# audio.net
KiCad netlist of a schematic drawn in EAGLE
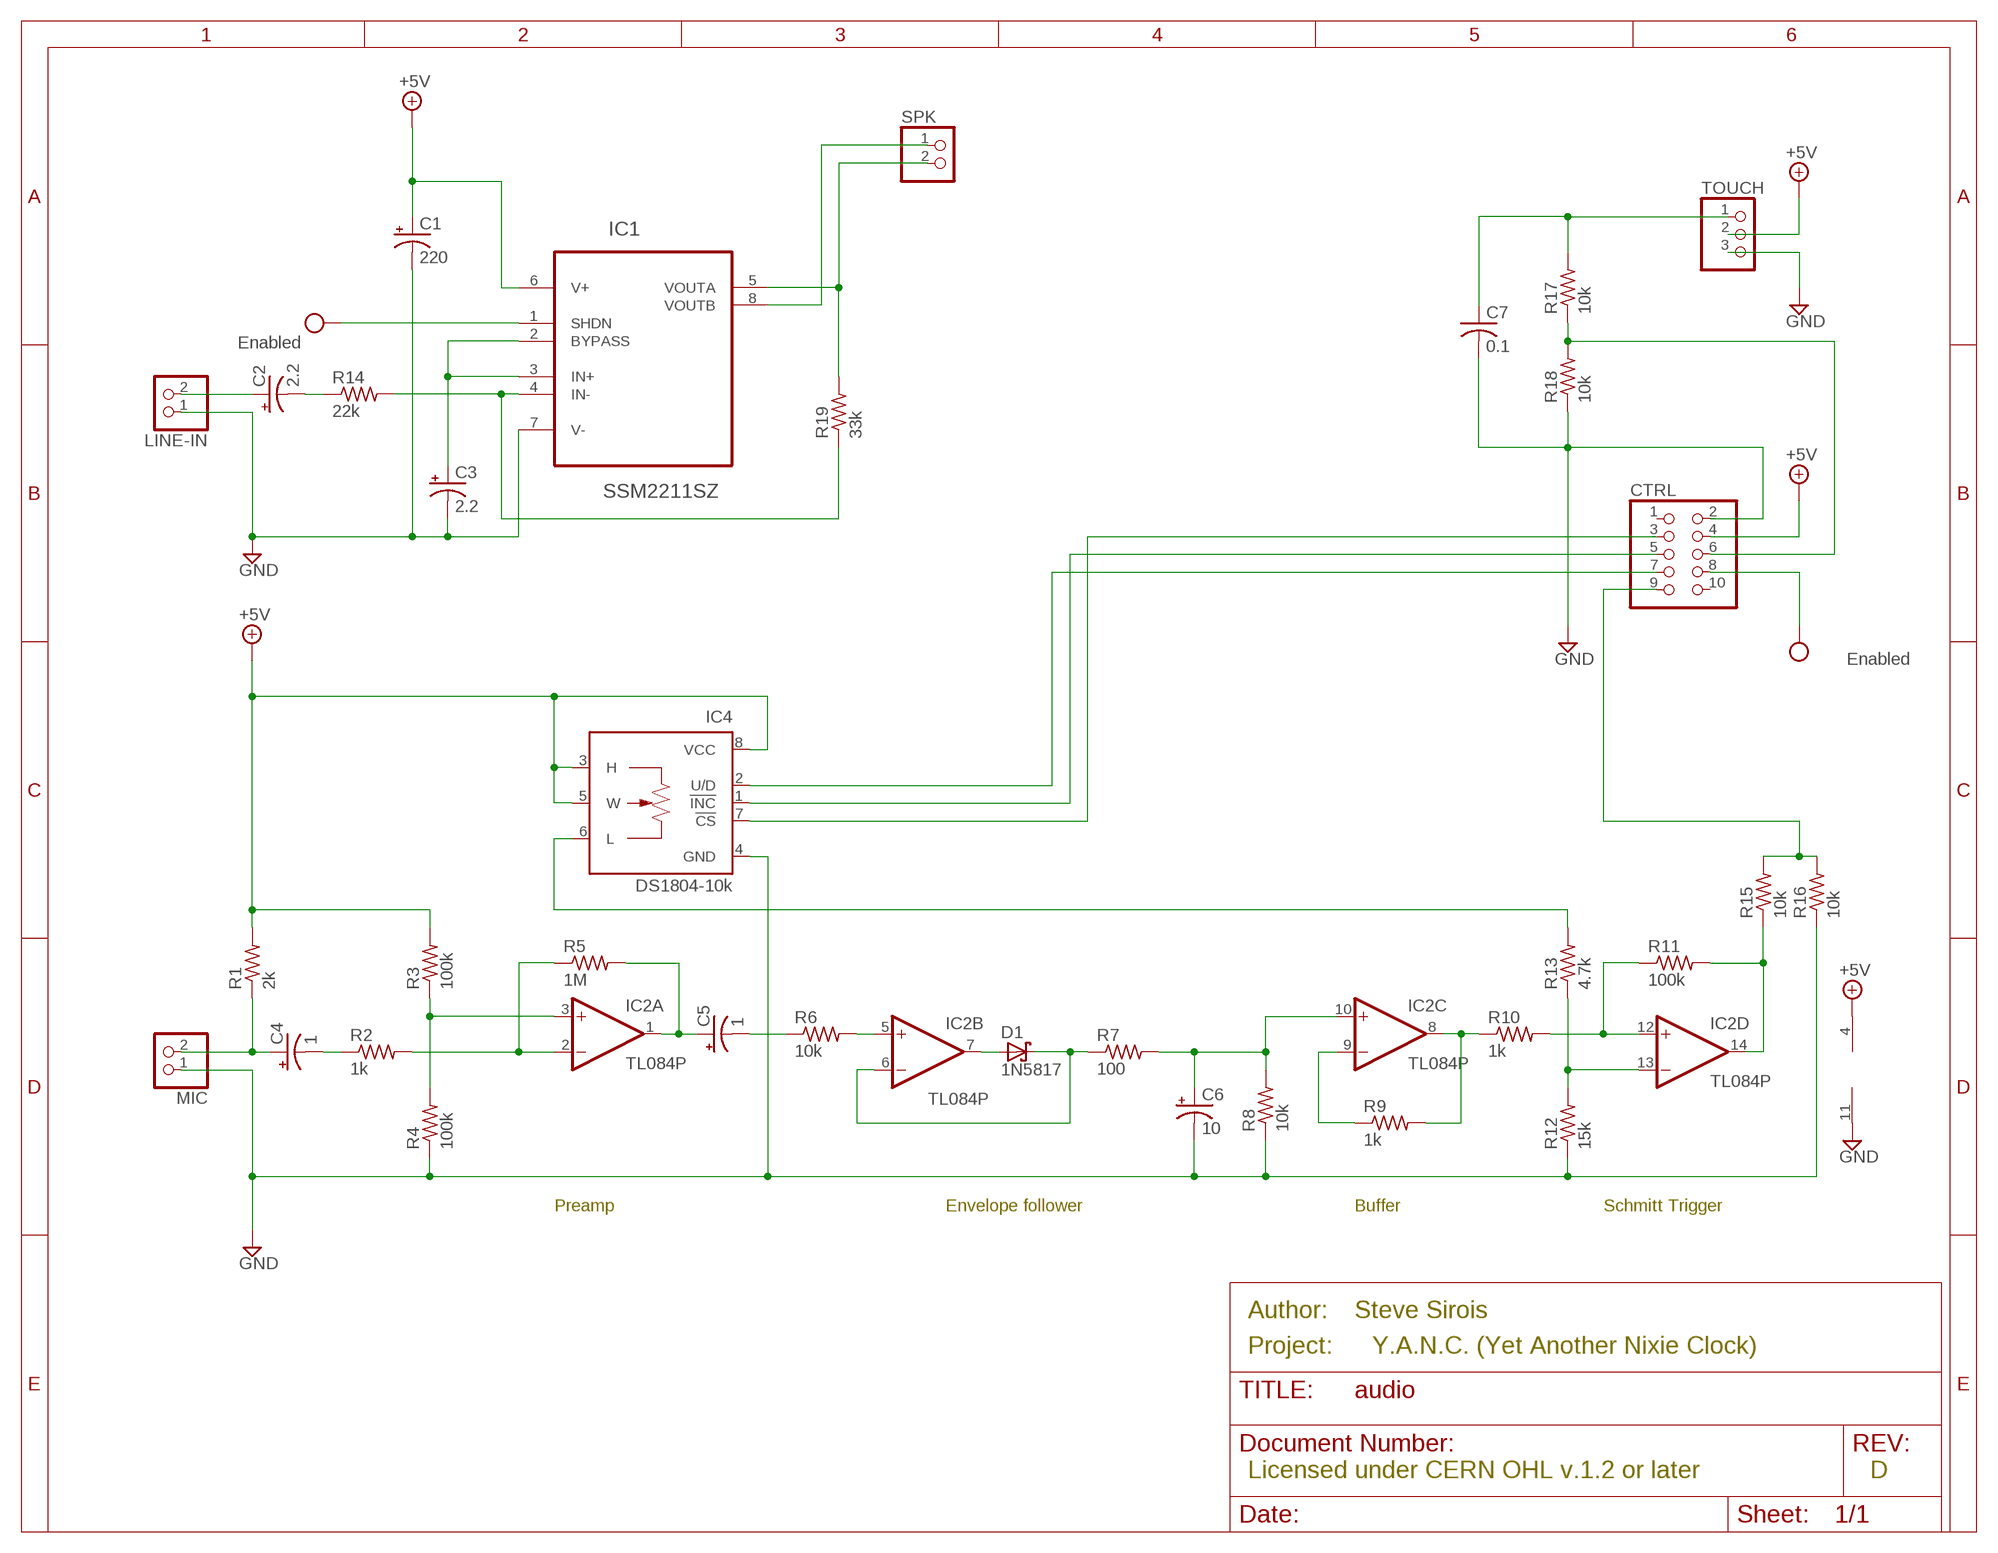
[diagram p0: schematic, sheet 1]

(export (version "E")
  (design (tool "Eeschema 10.0.6"))
  (components
    (comp (ref "C1")
      (value "220")
      (footprint "eagle-import:E3,5-10")
      (libsource (lib "eagle-import") (part "CPOL-USE3.5-10"))
    )
    (comp (ref "C2")
      (value "2.2")
      (footprint "eagle-import:E3,5-8")
      (libsource (lib "eagle-import") (part "CPOL-USE3.5-8"))
    )
    (comp (ref "C3")
      (value "2.2")
      (footprint "eagle-import:E3,5-8")
      (libsource (lib "eagle-import") (part "CPOL-USE3.5-8"))
    )
    (comp (ref "C4")
      (value "1")
      (footprint "eagle-import:E2-4")
      (libsource (lib "eagle-import") (part "CPOL-USE2-4"))
    )
    (comp (ref "C5")
      (value "1")
      (footprint "eagle-import:E2-4")
      (libsource (lib "eagle-import") (part "CPOL-USE2-4"))
    )
    (comp (ref "C6")
      (value "10")
      (footprint "eagle-import:E2-4")
      (libsource (lib "eagle-import") (part "CPOL-USE2-4"))
    )
    (comp (ref "C7")
      (value "0.1")
      (footprint "eagle-import:C025-024X044")
      (libsource (lib "eagle-import") (part "C-US025-024X044"))
    )
    (comp (ref "CTRL")
      (value "PINHD-2X5")
      (footprint "eagle-import:2X05")
      (libsource (lib "eagle-import") (part "PINHD-2X5"))
    )
    (comp (ref "D1")
      (value "1N5817")
      (footprint "eagle-import:DO41-7")
      (libsource (lib "eagle-import") (part "SCHOTTKY-DIODEDO41-7"))
    )
    (comp (ref "IC1")
      (value "SSM2211SZ")
      (footprint "eagle-import:SOIC127P600X175-8N")
      (libsource (lib "eagle-import") (part "SSM2211SZ"))
    )
    (comp (ref "IC2")
      (value "TL084P")
      (footprint "eagle-import:DIL14")
      (libsource (lib "eagle-import") (part "TL084P"))
    )
    (comp (ref "IC4")
      (value "DS1804-10k")
      (footprint "eagle-import:DIL08")
      (fields (field (name "MF") "INTERSIL") (field (name "MPN") "X9C102P"))
      (libsource (lib "eagle-import") (part "X9C102P"))
    )
    (comp (ref "LINE-IN")
      (value "PINHD-1X2")
      (footprint "eagle-import:1X02")
      (libsource (lib "eagle-import") (part "PINHD-1X2"))
    )
    (comp (ref "MIC")
      (value "PINHD-1X2")
      (footprint "eagle-import:1X02")
      (libsource (lib "eagle-import") (part "PINHD-1X2"))
    )
    (comp (ref "R1")
      (value "2k")
      (footprint "eagle-import:0204V")
      (libsource (lib "eagle-import") (part "R-US_0204/2V"))
    )
    (comp (ref "R2")
      (value "1k")
      (footprint "eagle-import:0204V")
      (libsource (lib "eagle-import") (part "R-US_0204/2V"))
    )
    (comp (ref "R3")
      (value "100k")
      (footprint "eagle-import:0204V")
      (libsource (lib "eagle-import") (part "R-US_0204/2V"))
    )
    (comp (ref "R4")
      (value "100k")
      (footprint "eagle-import:0204V")
      (libsource (lib "eagle-import") (part "R-US_0204/2V"))
    )
    (comp (ref "R5")
      (value "1M")
      (footprint "eagle-import:0204V")
      (libsource (lib "eagle-import") (part "R-US_0204/2V"))
    )
    (comp (ref "R6")
      (value "10k")
      (footprint "eagle-import:0204V")
      (libsource (lib "eagle-import") (part "R-US_0204/2V"))
    )
    (comp (ref "R7")
      (value "100")
      (footprint "eagle-import:0204V")
      (libsource (lib "eagle-import") (part "R-US_0204/2V"))
    )
    (comp (ref "R8")
      (value "10k")
      (footprint "eagle-import:0204V")
      (libsource (lib "eagle-import") (part "R-US_0204/2V"))
    )
    (comp (ref "R9")
      (value "1k")
      (footprint "eagle-import:0204V")
      (libsource (lib "eagle-import") (part "R-US_0204/2V"))
    )
    (comp (ref "R10")
      (value "1k")
      (footprint "eagle-import:0204V")
      (libsource (lib "eagle-import") (part "R-US_0204/2V"))
    )
    (comp (ref "R11")
      (value "100k")
      (footprint "eagle-import:0204V")
      (libsource (lib "eagle-import") (part "R-US_0204/2V"))
    )
    (comp (ref "R12")
      (value "15k")
      (footprint "eagle-import:0204V")
      (libsource (lib "eagle-import") (part "R-US_0204/2V"))
    )
    (comp (ref "R13")
      (value "4.7k")
      (footprint "eagle-import:0204V")
      (libsource (lib "eagle-import") (part "R-US_0204/2V"))
    )
    (comp (ref "R14")
      (value "22k")
      (footprint "eagle-import:0204V")
      (libsource (lib "eagle-import") (part "R-US_0204/2V"))
    )
    (comp (ref "R15")
      (value "10k")
      (footprint "eagle-import:0204V")
      (libsource (lib "eagle-import") (part "R-US_0204/2V"))
    )
    (comp (ref "R16")
      (value "10k")
      (footprint "eagle-import:0204V")
      (libsource (lib "eagle-import") (part "R-US_0204/2V"))
    )
    (comp (ref "R17")
      (value "10k")
      (footprint "eagle-import:0204V")
      (libsource (lib "eagle-import") (part "R-US_0204/2V"))
    )
    (comp (ref "R18")
      (value "10k")
      (footprint "eagle-import:0204V")
      (libsource (lib "eagle-import") (part "R-US_0204/2V"))
    )
    (comp (ref "R19")
      (value "33k")
      (footprint "eagle-import:0204V")
      (libsource (lib "eagle-import") (part "R-US_0204/2V"))
    )
    (comp (ref "SPK")
      (value "PINHD-1X2")
      (footprint "eagle-import:1X02")
      (libsource (lib "eagle-import") (part "PINHD-1X2"))
    )
    (comp (ref "TOUCH")
      (value "PINHD-1X3")
      (footprint "eagle-import:1X03")
      (libsource (lib "eagle-import") (part "PINHD-1X3"))
    )
  )
  (nets
    (net (code "1") (name "+5V") (class "Default")
      (node (ref "C1") (pin "+") (pinfunction "+_+") (pintype "passive"))
      (node (ref "CTRL") (pin "4") (pinfunction "4_4") (pintype "passive"))
      (node (ref "IC1") (pin "6") (pinfunction "V+_6") (pintype "power_in"))
      (node (ref "IC2") (pin "4") (pinfunction "V+_4") (pintype "power_in"))
      (node (ref "IC4") (pin "3") (pinfunction "H_3") (pintype "passive"))
      (node (ref "IC4") (pin "5") (pinfunction "W_5") (pintype "passive"))
      (node (ref "IC4") (pin "8") (pinfunction "VCC_8") (pintype "power_in"))
      (node (ref "R1") (pin "2") (pinfunction "2_2") (pintype "passive"))
      (node (ref "R3") (pin "2") (pinfunction "2_2") (pintype "passive"))
      (node (ref "TOUCH") (pin "2") (pinfunction "2_2") (pintype "passive"))
    )
    (net (code "2") (name "Enabled") (class "Default")
      (node (ref "CTRL") (pin "8") (pinfunction "8_8") (pintype "passive"))
      (node (ref "IC1") (pin "1") (pinfunction "SHDN_1") (pintype "passive"))
    )
    (net (code "3") (name "GND") (class "Default")
      (node (ref "C1") (pin "-") (pinfunction "-_-") (pintype "passive"))
      (node (ref "C3") (pin "-") (pinfunction "-_-") (pintype "passive"))
      (node (ref "C6") (pin "-") (pinfunction "-_-") (pintype "passive"))
      (node (ref "C7") (pin "2") (pinfunction "2_2") (pintype "passive"))
      (node (ref "CTRL") (pin "2") (pinfunction "2_2") (pintype "passive"))
      (node (ref "IC1") (pin "7") (pinfunction "V-_7") (pintype "power_in"))
      (node (ref "IC2") (pin "11") (pinfunction "V-_11") (pintype "power_in"))
      (node (ref "IC4") (pin "4") (pinfunction "GND_4") (pintype "power_in"))
      (node (ref "LINE-IN") (pin "1") (pinfunction "1_1") (pintype "passive"))
      (node (ref "MIC") (pin "1") (pinfunction "1_1") (pintype "passive"))
      (node (ref "R12") (pin "1") (pinfunction "1_1") (pintype "passive"))
      (node (ref "R16") (pin "1") (pinfunction "1_1") (pintype "passive"))
      (node (ref "R18") (pin "1") (pinfunction "1_1") (pintype "passive"))
      (node (ref "R4") (pin "1") (pinfunction "1_1") (pintype "passive"))
      (node (ref "R8") (pin "1") (pinfunction "1_1") (pintype "passive"))
      (node (ref "TOUCH") (pin "3") (pinfunction "3_3") (pintype "passive"))
    )
    (net (code "4") (name "Net-(C2-Pad+)") (class "Default")
      (node (ref "C2") (pin "+") (pinfunction "+_+") (pintype "passive"))
      (node (ref "LINE-IN") (pin "2") (pinfunction "2_2") (pintype "passive"))
    )
    (net (code "5") (name "Net-(C2-Pad-)") (class "Default")
      (node (ref "C2") (pin "-") (pinfunction "-_-") (pintype "passive"))
      (node (ref "R14") (pin "1") (pinfunction "1_1") (pintype "passive"))
    )
    (net (code "6") (name "Net-(C4-Pad+)") (class "Default")
      (node (ref "C4") (pin "+") (pinfunction "+_+") (pintype "passive"))
      (node (ref "MIC") (pin "2") (pinfunction "2_2") (pintype "passive"))
      (node (ref "R1") (pin "1") (pinfunction "1_1") (pintype "passive"))
    )
    (net (code "7") (name "Net-(C4-Pad-)") (class "Default")
      (node (ref "C4") (pin "-") (pinfunction "-_-") (pintype "passive"))
      (node (ref "R2") (pin "1") (pinfunction "1_1") (pintype "passive"))
    )
    (net (code "8") (name "Net-(C5-Pad-)") (class "Default")
      (node (ref "C5") (pin "-") (pinfunction "-_-") (pintype "passive"))
      (node (ref "R6") (pin "1") (pinfunction "1_1") (pintype "passive"))
    )
    (net (code "9") (name "Net-(C7-Pad1)") (class "Default")
      (node (ref "C7") (pin "1") (pinfunction "1_1") (pintype "passive"))
      (node (ref "R17") (pin "2") (pinfunction "2_2") (pintype "passive"))
      (node (ref "TOUCH") (pin "1") (pinfunction "1_1") (pintype "passive"))
    )
    (net (code "10") (name "Net-(CTRL-Pad6)") (class "Default")
      (node (ref "CTRL") (pin "6") (pinfunction "6_6") (pintype "passive"))
      (node (ref "R17") (pin "1") (pinfunction "1_1") (pintype "passive"))
      (node (ref "R18") (pin "2") (pinfunction "2_2") (pintype "passive"))
    )
    (net (code "11") (name "Net-(CTRL-Pad9)") (class "Default")
      (node (ref "CTRL") (pin "9") (pinfunction "9_9") (pintype "passive"))
      (node (ref "R15") (pin "2") (pinfunction "2_2") (pintype "passive"))
      (node (ref "R16") (pin "2") (pinfunction "2_2") (pintype "passive"))
    )
    (net (code "12") (name "Net-(IC1-BYPASS)") (class "Default")
      (node (ref "C3") (pin "+") (pinfunction "+_+") (pintype "passive"))
      (node (ref "IC1") (pin "2") (pinfunction "BYPASS_2") (pintype "passive"))
      (node (ref "IC1") (pin "3") (pinfunction "IN+_3") (pintype "input"))
    )
    (net (code "13") (name "Net-(IC1-IN-)") (class "Default")
      (node (ref "IC1") (pin "4") (pinfunction "IN-_4") (pintype "input"))
      (node (ref "R14") (pin "2") (pinfunction "2_2") (pintype "passive"))
      (node (ref "R19") (pin "1") (pinfunction "1_1") (pintype "passive"))
    )
    (net (code "14") (name "Net-(IC1-VOUTA)") (class "Default")
      (node (ref "IC1") (pin "5") (pinfunction "VOUTA_5") (pintype "output"))
      (node (ref "R19") (pin "2") (pinfunction "2_2") (pintype "passive"))
      (node (ref "SPK") (pin "2") (pinfunction "2_2") (pintype "passive"))
    )
    (net (code "15") (name "Net-(IC1-VOUTB)") (class "Default")
      (node (ref "IC1") (pin "8") (pinfunction "VOUTB_8") (pintype "output"))
      (node (ref "SPK") (pin "1") (pinfunction "1_1") (pintype "passive"))
    )
    (net (code "16") (name "Net-(IC2A-+IN)") (class "Default")
      (node (ref "IC2") (pin "3") (pinfunction "+IN_3") (pintype "input"))
      (node (ref "R3") (pin "1") (pinfunction "1_1") (pintype "passive"))
      (node (ref "R4") (pin "2") (pinfunction "2_2") (pintype "passive"))
    )
    (net (code "17") (name "Net-(IC2A--IN)") (class "Default")
      (node (ref "IC2") (pin "2") (pinfunction "-IN_2") (pintype "input"))
      (node (ref "R2") (pin "2") (pinfunction "2_2") (pintype "passive"))
      (node (ref "R5") (pin "1") (pinfunction "1_1") (pintype "passive"))
    )
    (net (code "18") (name "Net-(IC2A-OUT)") (class "Default")
      (node (ref "C5") (pin "+") (pinfunction "+_+") (pintype "passive"))
      (node (ref "IC2") (pin "1") (pinfunction "OUT_1") (pintype "output"))
      (node (ref "R5") (pin "2") (pinfunction "2_2") (pintype "passive"))
    )
    (net (code "19") (name "Net-(IC2B-+IN)") (class "Default")
      (node (ref "IC2") (pin "5") (pinfunction "+IN_5") (pintype "input"))
      (node (ref "R6") (pin "2") (pinfunction "2_2") (pintype "passive"))
    )
    (net (code "20") (name "Net-(IC2B--IN)") (class "Default")
      (node (ref "D1") (pin "C") (pinfunction "C_C") (pintype "passive"))
      (node (ref "IC2") (pin "6") (pinfunction "-IN_6") (pintype "input"))
      (node (ref "R7") (pin "1") (pinfunction "1_1") (pintype "passive"))
    )
    (net (code "21") (name "Net-(IC2B-OUT)") (class "Default")
      (node (ref "D1") (pin "A") (pinfunction "A_A") (pintype "passive"))
      (node (ref "IC2") (pin "7") (pinfunction "OUT_7") (pintype "output"))
    )
    (net (code "22") (name "Net-(IC2C-+IN)") (class "Default")
      (node (ref "C6") (pin "+") (pinfunction "+_+") (pintype "passive"))
      (node (ref "IC2") (pin "10") (pinfunction "+IN_10") (pintype "input"))
      (node (ref "R7") (pin "2") (pinfunction "2_2") (pintype "passive"))
      (node (ref "R8") (pin "2") (pinfunction "2_2") (pintype "passive"))
    )
    (net (code "23") (name "Net-(IC2C--IN)") (class "Default")
      (node (ref "IC2") (pin "9") (pinfunction "-IN_9") (pintype "input"))
      (node (ref "R9") (pin "1") (pinfunction "1_1") (pintype "passive"))
    )
    (net (code "24") (name "Net-(IC2C-OUT)") (class "Default")
      (node (ref "IC2") (pin "8") (pinfunction "OUT_8") (pintype "output"))
      (node (ref "R10") (pin "1") (pinfunction "1_1") (pintype "passive"))
      (node (ref "R9") (pin "2") (pinfunction "2_2") (pintype "passive"))
    )
    (net (code "25") (name "Net-(IC2D-+IN)") (class "Default")
      (node (ref "IC2") (pin "12") (pinfunction "+IN_12") (pintype "input"))
      (node (ref "R10") (pin "2") (pinfunction "2_2") (pintype "passive"))
      (node (ref "R11") (pin "1") (pinfunction "1_1") (pintype "passive"))
    )
    (net (code "26") (name "Net-(IC2D--IN)") (class "Default")
      (node (ref "IC2") (pin "13") (pinfunction "-IN_13") (pintype "input"))
      (node (ref "R12") (pin "2") (pinfunction "2_2") (pintype "passive"))
      (node (ref "R13") (pin "1") (pinfunction "1_1") (pintype "passive"))
    )
    (net (code "27") (name "Net-(IC2D-OUT)") (class "Default")
      (node (ref "IC2") (pin "14") (pinfunction "OUT_14") (pintype "output"))
      (node (ref "R11") (pin "2") (pinfunction "2_2") (pintype "passive"))
      (node (ref "R15") (pin "1") (pinfunction "1_1") (pintype "passive"))
    )
    (net (code "28") (name "Net-(IC4-L)") (class "Default")
      (node (ref "IC4") (pin "6") (pinfunction "L_6") (pintype "passive"))
      (node (ref "R13") (pin "2") (pinfunction "2_2") (pintype "passive"))
    )
    (net (code "29") (name "Net-(IC4-U{slash}D)") (class "Default")
      (node (ref "CTRL") (pin "7") (pinfunction "7_7") (pintype "passive"))
      (node (ref "IC4") (pin "2") (pinfunction "U/D_2") (pintype "input"))
    )
    (net (code "30") (name "Net-(IC4-~{CS})") (class "Default")
      (node (ref "CTRL") (pin "3") (pinfunction "3_3") (pintype "passive"))
      (node (ref "IC4") (pin "7") (pinfunction "~{CS}_7") (pintype "input"))
    )
    (net (code "31") (name "Net-(IC4-~{INC})") (class "Default")
      (node (ref "CTRL") (pin "5") (pinfunction "5_5") (pintype "passive"))
      (node (ref "IC4") (pin "1") (pinfunction "~{INC}_1") (pintype "input"))
    )
    (net (code "32") (name "unconnected-(CTRL-Pad1)") (class "Default")
      (node (ref "CTRL") (pin "1") (pinfunction "1_1") (pintype "passive"))
    )
    (net (code "33") (name "unconnected-(CTRL-Pad10)") (class "Default")
      (node (ref "CTRL") (pin "10") (pinfunction "10_10") (pintype "passive"))
    )
  )
)
